# MOD-W_V02.net
KiCad netlist of a schematic drawn in EAGLE
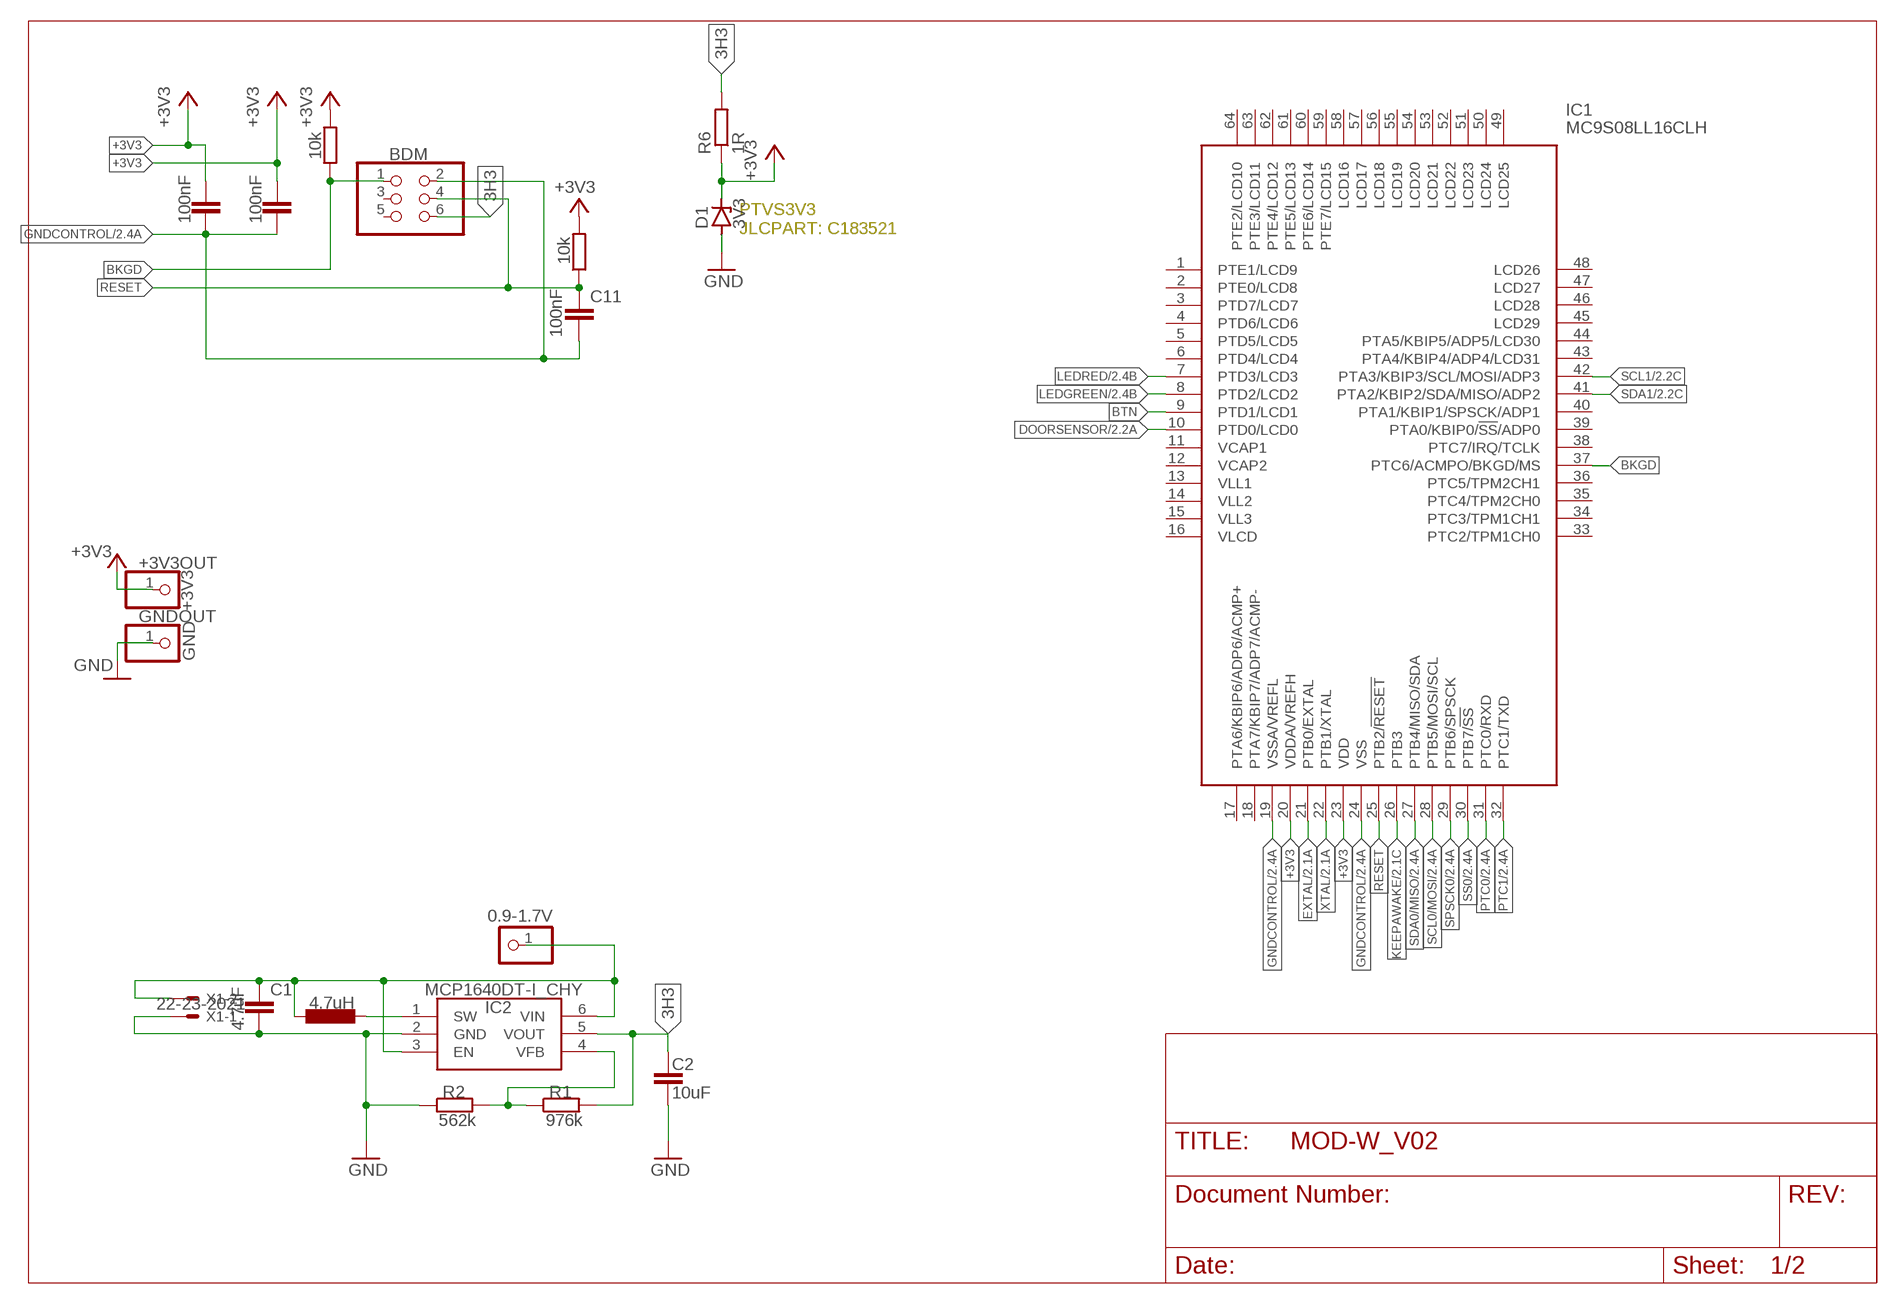
[diagram p0: schematic, sheet 1]
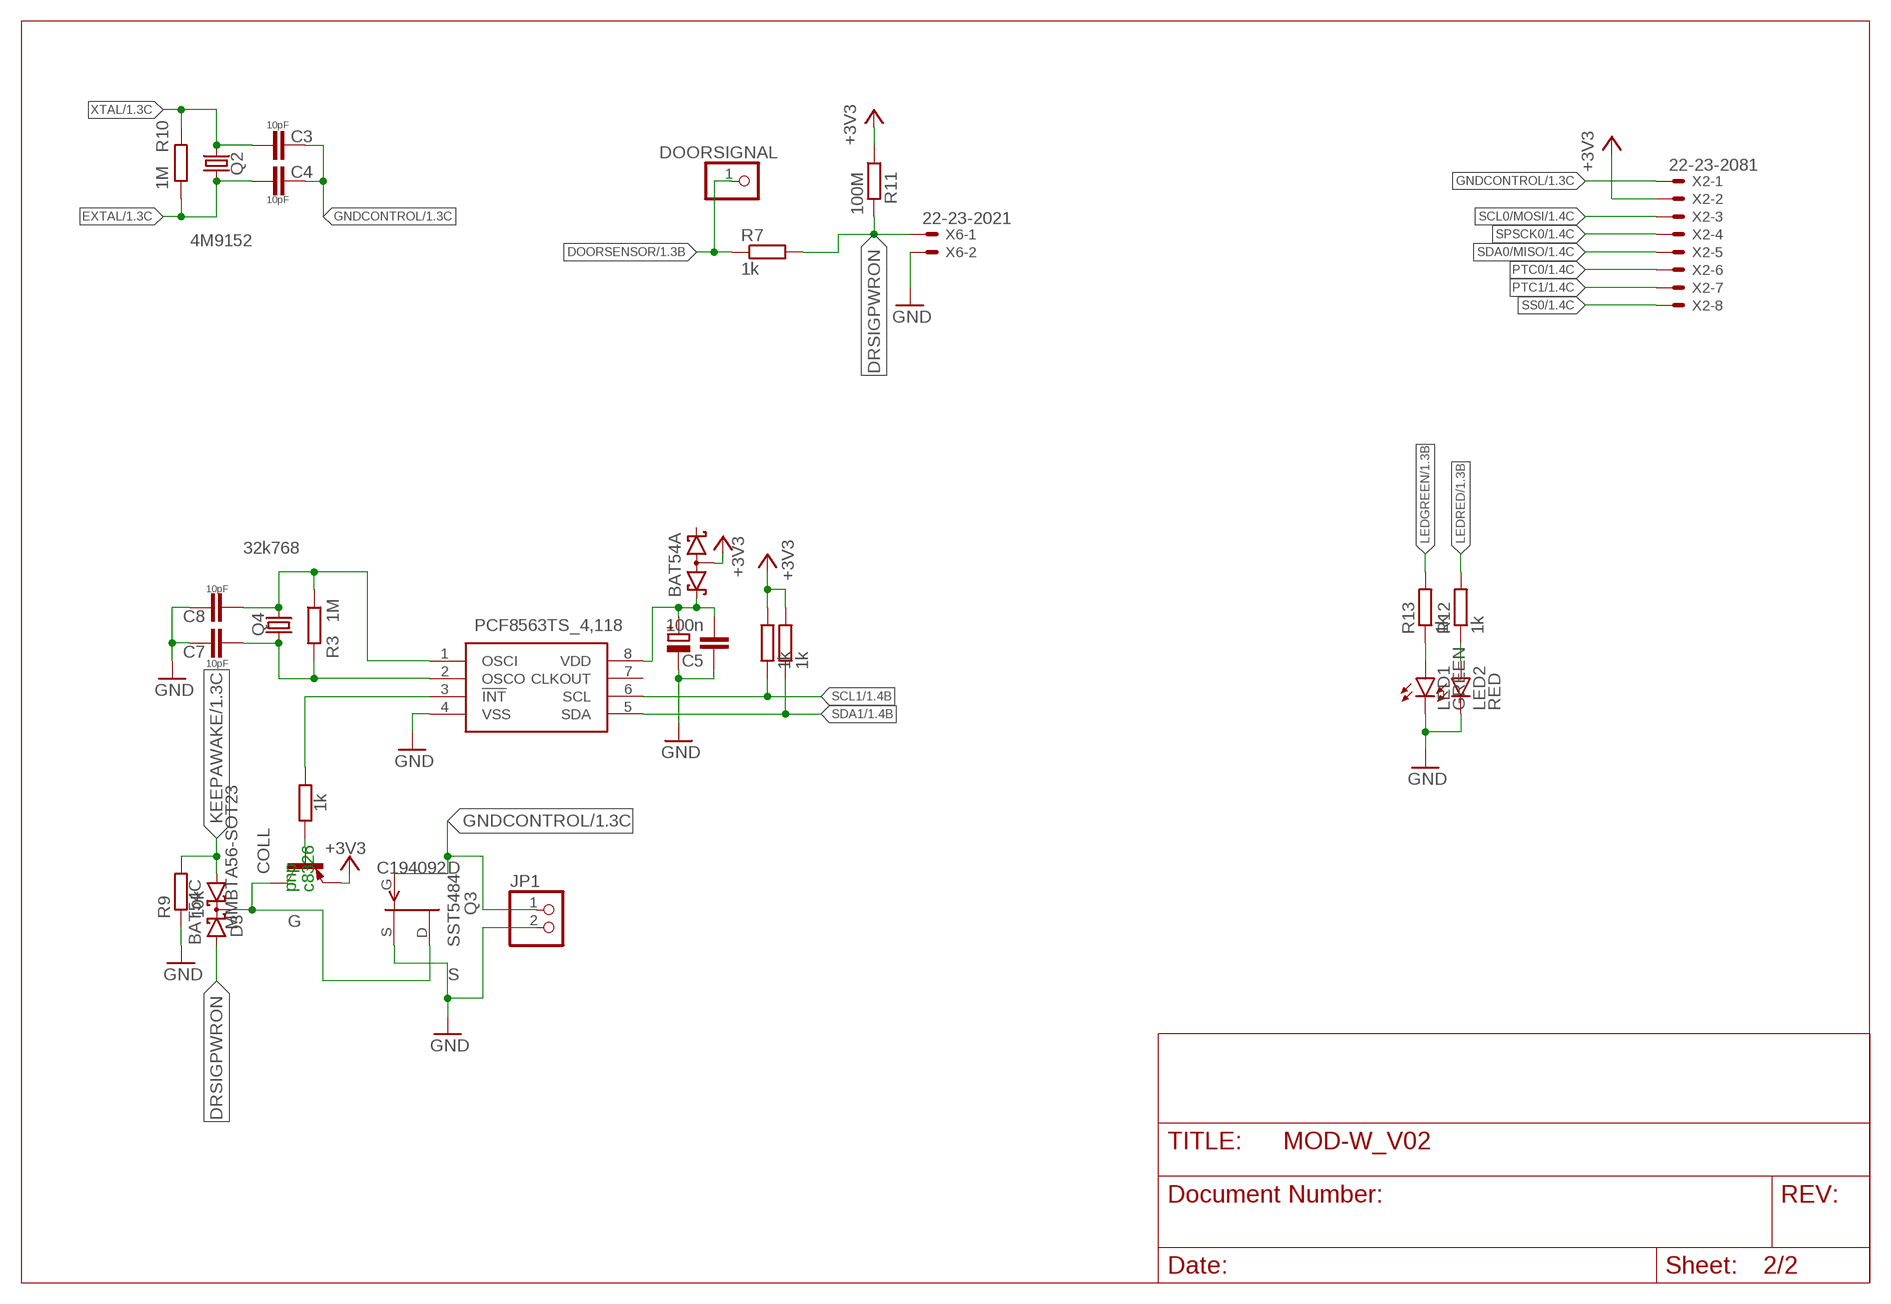
[diagram p1: schematic, sheet 2]

(export (version "E")
  (design (tool "Eeschema 10.0.6"))
  (components
    (comp (ref "+3V3OUT")
      (value "+3V3")
      (footprint "eagle-import:1X01")
      (libsource (lib "eagle-import") (part "PINHD-1X1"))
    )
    (comp (ref "BAT")
      (value "0.9-1.7V")
      (footprint "eagle-import:1X01")
      (libsource (lib "eagle-import") (part "PINHD-1X1"))
    )
    (comp (ref "BDM")
      (value "PINHD-2X3")
      (footprint "eagle-import:2X03")
      (libsource (lib "eagle-import") (part "PINHD-2X3"))
    )
    (comp (ref "C1")
      (value "4.7uF")
      (footprint "eagle-import:C0805")
      (libsource (lib "eagle-import") (part "C-EUC0805"))
    )
    (comp (ref "C2")
      (value "10uF")
      (footprint "eagle-import:C0805")
      (libsource (lib "eagle-import") (part "C-EUC0805"))
    )
    (comp (ref "C9")
      (value "100nF")
      (footprint "eagle-import:C0805")
      (libsource (lib "eagle-import") (part "C-EUC0805"))
    )
    (comp (ref "C10")
      (value "100nF")
      (footprint "eagle-import:C0805")
      (libsource (lib "eagle-import") (part "C-EUC0805"))
    )
    (comp (ref "C11")
      (value "100nF")
      (footprint "eagle-import:C0805")
      (libsource (lib "eagle-import") (part "C-EUC0805"))
    )
    (comp (ref "D1")
      (value "3V3")
      (footprint "eagle-import:SOD80C")
      (libsource (lib "eagle-import") (part "ZENER-DIODESOD80C"))
    )
    (comp (ref "GNDOUT")
      (value "GND")
      (footprint "eagle-import:1X01")
      (libsource (lib "eagle-import") (part "PINHD-1X1"))
    )
    (comp (ref "IC1")
      (value "MC9S08LL16CLH")
      (footprint "eagle-import:QFP50P1200X1200X160-64N")
      (fields (field (name "MOUSER_PART_NUMBER") "841-MC9S08LL16CLH"))
      (libsource (lib "eagle-import") (part "MC9S08LL16CLH"))
    )
    (comp (ref "IC2")
      (value "MCP1640DT-I_CHY")
      (footprint "eagle-import:SOT95P270X145-6N")
      (fields
        (field (name "ARROW_PART_NUMBER") "MCP1640DT-I/CHY")
        (field (name "MOUSER_PART_NUMBER") "579-MCP1640DT-I/CHY")
      )
      (libsource (lib "eagle-import") (part "MCP1640DT-I_CHY"))
    )
    (comp (ref "L1")
      (value "4.7uH")
      (footprint "eagle-import:L2012C")
      (libsource (lib "eagle-import") (part "L-EUL2012C"))
    )
    (comp (ref "R1")
      (value "976k")
      (footprint "eagle-import:R0805")
      (libsource (lib "eagle-import") (part "R-EU_R0805"))
    )
    (comp (ref "R2")
      (value "562k")
      (footprint "eagle-import:R0805")
      (libsource (lib "eagle-import") (part "R-EU_R0805"))
    )
    (comp (ref "R6")
      (value "1R")
      (footprint "eagle-import:R0805")
      (libsource (lib "eagle-import") (part "R-EU_R0805"))
    )
    (comp (ref "R16")
      (value "10k")
      (footprint "eagle-import:R0805")
      (libsource (lib "eagle-import") (part "R-EU_R0805"))
    )
    (comp (ref "R17")
      (value "10k")
      (footprint "eagle-import:R0805")
      (libsource (lib "eagle-import") (part "R-EU_R0805"))
    )
    (comp (ref "X1")
      (value "22-23-2021")
      (footprint "eagle-import:22-23-2021")
      (fields (field (name "MF") "MOLEX"))
      (libsource (lib "eagle-import") (part "22-23-2021"))
    )
    (comp (ref "C3")
      (value "10pF")
      (footprint "eagle-import:C0805")
      (libsource (lib "eagle-import") (part "C-EUC0805"))
    )
    (comp (ref "C4")
      (value "10pF")
      (footprint "eagle-import:C0805")
      (libsource (lib "eagle-import") (part "C-EUC0805"))
    )
    (comp (ref "C5")
      (value "100n")
      (footprint "eagle-import:C0805")
      (libsource (lib "eagle-import") (part "C-EUC0805"))
    )
    (comp (ref "C6")
      (value "100u")
      (footprint "eagle-import:PANASONIC_E")
      (libsource (lib "eagle-import") (part "CPOL-EUE"))
    )
    (comp (ref "C7")
      (value "10pF")
      (footprint "eagle-import:C0805")
      (libsource (lib "eagle-import") (part "C-EUC0805"))
    )
    (comp (ref "C8")
      (value "10pF")
      (footprint "eagle-import:C0805")
      (libsource (lib "eagle-import") (part "C-EUC0805"))
    )
    (comp (ref "D2")
      (value "BAT54A")
      (footprint "eagle-import:SOT23")
      (libsource (lib "eagle-import") (part "BAT54A"))
    )
    (comp (ref "D3")
      (value "BAT54C")
      (footprint "eagle-import:SOT23")
      (libsource (lib "eagle-import") (part "BAT54C"))
    )
    (comp (ref "DOORSIGNAL")
      (value "PINHD-1X1")
      (footprint "eagle-import:1X01")
      (libsource (lib "eagle-import") (part "PINHD-1X1"))
    )
    (comp (ref "IC3")
      (value "PCF8563TS_4,118")
      (footprint "eagle-import:SOP65P490X110-8N")
      (fields
        (field (name "ARROW_PART_NUMBER") "PCF8563TS/4,118")
        (field (name "MOUSER_PART_NUMBER") "771-PCF8563TS-T")
      )
      (libsource (lib "eagle-import") (part "PCF8563TS_4,118"))
    )
    (comp (ref "JP1")
      (value "PINHD-1X2")
      (footprint "eagle-import:1X02")
      (libsource (lib "eagle-import") (part "PINHD-1X2"))
    )
    (comp (ref "LED1")
      (value "GREEN")
      (footprint "eagle-import:CHIP-LED0805")
      (libsource (lib "eagle-import") (part "LEDCHIP-LED0805"))
    )
    (comp (ref "LED2")
      (value "RED")
      (footprint "eagle-import:CHIP-LED0805")
      (libsource (lib "eagle-import") (part "LEDCHIP-LED0805"))
    )
    (comp (ref "Q1")
      (value "MMBTA56-SOT23")
      (footprint "eagle-import:SOT23")
      (libsource (lib "eagle-import") (part "-?SOT23MMBTA56"))
    )
    (comp (ref "Q2")
      (value "4M9152")
      (footprint "eagle-import:HC49UP")
      (libsource (lib "eagle-import") (part "CRYSTALHC49UP"))
    )
    (comp (ref "Q3")
      (value "SST5484")
      (footprint "eagle-import:SOT23")
      (libsource (lib "eagle-import") (part "?548SST4"))
    )
    (comp (ref "Q4")
      (value "32k768")
      (footprint "eagle-import:TC38H")
      (libsource (lib "eagle-import") (part "CRYSTALTC38H"))
    )
    (comp (ref "R3")
      (value "1M")
      (footprint "eagle-import:R0805")
      (libsource (lib "eagle-import") (part "R-EU_R0805"))
    )
    (comp (ref "R4")
      (value "1k")
      (footprint "eagle-import:R0805")
      (libsource (lib "eagle-import") (part "R-EU_R0805"))
    )
    (comp (ref "R5")
      (value "1k")
      (footprint "eagle-import:R0805")
      (libsource (lib "eagle-import") (part "R-EU_R0805"))
    )
    (comp (ref "R7")
      (value "1k")
      (footprint "eagle-import:R0805")
      (libsource (lib "eagle-import") (part "R-EU_R0805"))
    )
    (comp (ref "R8")
      (value "1k")
      (footprint "eagle-import:R0805")
      (libsource (lib "eagle-import") (part "R-EU_R0805"))
    )
    (comp (ref "R9")
      (value "10k")
      (footprint "eagle-import:R0805")
      (libsource (lib "eagle-import") (part "R-EU_R0805"))
    )
    (comp (ref "R10")
      (value "1M")
      (footprint "eagle-import:R0805")
      (libsource (lib "eagle-import") (part "R-EU_R0805"))
    )
    (comp (ref "R11")
      (value "100M")
      (footprint "eagle-import:R0805")
      (libsource (lib "eagle-import") (part "R-EU_R0805"))
    )
    (comp (ref "R12")
      (value "1k")
      (footprint "eagle-import:R0805")
      (libsource (lib "eagle-import") (part "R-EU_R0805"))
    )
    (comp (ref "R13")
      (value "1k")
      (footprint "eagle-import:R0805")
      (libsource (lib "eagle-import") (part "R-EU_R0805"))
    )
    (comp (ref "X2")
      (value "22-23-2081")
      (footprint "eagle-import:22-23-2081")
      (fields (field (name "MF") "MOLEX"))
      (libsource (lib "eagle-import") (part "22-23-2081"))
    )
    (comp (ref "X6")
      (value "22-23-2021")
      (footprint "eagle-import:22-23-2021")
      (fields (field (name "MF") "MOLEX"))
      (libsource (lib "eagle-import") (part "22-23-2021"))
    )
  )
  (nets
    (net (code "1") (name "+3V3") (class "Default")
      (node (ref "+3V3OUT") (pin "1") (pinfunction "1_1") (pintype "passive"))
      (node (ref "C10") (pin "1") (pinfunction "1_1") (pintype "passive"))
      (node (ref "C9") (pin "1") (pinfunction "1_1") (pintype "passive"))
      (node (ref "D1") (pin "C") (pinfunction "C_C") (pintype "passive"))
      (node (ref "D2") (pin "3") (pinfunction "AA_3") (pintype "passive"))
      (node (ref "IC1") (pin "20") (pinfunction "VDDA/VREFH_20") (pintype "bidirectional"))
      (node (ref "IC1") (pin "23") (pinfunction "VDD_23") (pintype "bidirectional"))
      (node (ref "Q1") (pin "2") (pinfunction "E_2") (pintype "passive"))
      (node (ref "R11") (pin "1") (pinfunction "1_1") (pintype "passive"))
      (node (ref "R16") (pin "2") (pinfunction "2_2") (pintype "passive"))
      (node (ref "R17") (pin "2") (pinfunction "2_2") (pintype "passive"))
      (node (ref "R4") (pin "2") (pinfunction "2_2") (pintype "passive"))
      (node (ref "R5") (pin "2") (pinfunction "2_2") (pintype "passive"))
      (node (ref "R6") (pin "1") (pinfunction "1_1") (pintype "passive"))
      (node (ref "X2") (pin "2") (pinfunction "S_2") (pintype "passive"))
    )
    (net (code "2") (name "3H3") (class "Default")
      (node (ref "BDM") (pin "6") (pinfunction "6_6") (pintype "passive"))
      (node (ref "C2") (pin "1") (pinfunction "1_1") (pintype "passive"))
      (node (ref "IC2") (pin "5") (pinfunction "VOUT_5") (pintype "output"))
      (node (ref "R1") (pin "2") (pinfunction "2_2") (pintype "passive"))
      (node (ref "R6") (pin "2") (pinfunction "2_2") (pintype "passive"))
    )
    (net (code "3") (name "BKGD") (class "Default")
      (node (ref "BDM") (pin "1") (pinfunction "1_1") (pintype "passive"))
      (node (ref "IC1") (pin "37") (pinfunction "PTC6/ACMPO/BKGD/MS_37") (pintype "bidirectional"))
      (node (ref "R16") (pin "1") (pinfunction "1_1") (pintype "passive"))
    )
    (net (code "4") (name "BTN") (class "Default")
      (node (ref "IC1") (pin "9") (pinfunction "PTD1/LCD1_9") (pintype "bidirectional"))
    )
    (net (code "5") (name "COLL") (class "Default")
      (node (ref "D3") (pin "3") (pinfunction "CC_3") (pintype "passive"))
      (node (ref "Q1") (pin "3") (pinfunction "C_3") (pintype "passive"))
      (node (ref "Q3") (pin "1") (pinfunction "D_1") (pintype "passive"))
    )
    (net (code "6") (name "DOORSENSOR") (class "Default")
      (node (ref "DOORSIGNAL") (pin "1") (pinfunction "1_1") (pintype "passive"))
      (node (ref "IC1") (pin "10") (pinfunction "PTD0/LCD0_10") (pintype "bidirectional"))
      (node (ref "R7") (pin "1") (pinfunction "1_1") (pintype "passive"))
    )
    (net (code "7") (name "DRSIGPWRON") (class "Default")
      (node (ref "D3") (pin "2") (pinfunction "A2_2") (pintype "passive"))
      (node (ref "R11") (pin "2") (pinfunction "2_2") (pintype "passive"))
      (node (ref "R7") (pin "2") (pinfunction "2_2") (pintype "passive"))
      (node (ref "X6") (pin "1") (pinfunction "S_1") (pintype "passive"))
    )
    (net (code "8") (name "EXTAL") (class "Default")
      (node (ref "C4") (pin "1") (pinfunction "1_1") (pintype "passive"))
      (node (ref "IC1") (pin "21") (pinfunction "PTB0/EXTAL_21") (pintype "bidirectional"))
      (node (ref "Q2") (pin "1") (pinfunction "1_1") (pintype "passive"))
      (node (ref "R10") (pin "1") (pinfunction "1_1") (pintype "passive"))
    )
    (net (code "9") (name "GND") (class "Default")
      (node (ref "C1") (pin "2") (pinfunction "2_2") (pintype "passive"))
      (node (ref "C2") (pin "2") (pinfunction "2_2") (pintype "passive"))
      (node (ref "C5") (pin "1") (pinfunction "1_1") (pintype "passive"))
      (node (ref "C6") (pin "-") (pinfunction "-_-") (pintype "passive"))
      (node (ref "C7") (pin "2") (pinfunction "2_2") (pintype "passive"))
      (node (ref "C8") (pin "2") (pinfunction "2_2") (pintype "passive"))
      (node (ref "D1") (pin "A") (pinfunction "A_A") (pintype "passive"))
      (node (ref "GNDOUT") (pin "1") (pinfunction "1_1") (pintype "passive"))
      (node (ref "IC2") (pin "2") (pinfunction "GND_2") (pintype "power_in"))
      (node (ref "IC3") (pin "4") (pinfunction "VSS_4") (pintype "bidirectional"))
      (node (ref "JP1") (pin "2") (pinfunction "2_2") (pintype "passive"))
      (node (ref "LED1") (pin "C") (pinfunction "C_C") (pintype "passive"))
      (node (ref "LED2") (pin "C") (pinfunction "C_C") (pintype "passive"))
      (node (ref "Q3") (pin "2") (pinfunction "S_2") (pintype "passive"))
      (node (ref "R2") (pin "1") (pinfunction "1_1") (pintype "passive"))
      (node (ref "R9") (pin "1") (pinfunction "1_1") (pintype "passive"))
      (node (ref "X1") (pin "1") (pinfunction "S_1") (pintype "passive"))
      (node (ref "X6") (pin "2") (pinfunction "S_2") (pintype "passive"))
    )
    (net (code "10") (name "GNDCONTROL") (class "Default")
      (node (ref "BDM") (pin "2") (pinfunction "2_2") (pintype "passive"))
      (node (ref "C10") (pin "2") (pinfunction "2_2") (pintype "passive"))
      (node (ref "C11") (pin "2") (pinfunction "2_2") (pintype "passive"))
      (node (ref "C3") (pin "2") (pinfunction "2_2") (pintype "passive"))
      (node (ref "C4") (pin "2") (pinfunction "2_2") (pintype "passive"))
      (node (ref "C9") (pin "2") (pinfunction "2_2") (pintype "passive"))
      (node (ref "IC1") (pin "19") (pinfunction "VSSA/VREFL_19") (pintype "bidirectional"))
      (node (ref "IC1") (pin "24") (pinfunction "VSS_24") (pintype "bidirectional"))
      (node (ref "JP1") (pin "1") (pinfunction "1_1") (pintype "passive"))
      (node (ref "Q3") (pin "3") (pinfunction "G_3") (pintype "passive"))
      (node (ref "X2") (pin "1") (pinfunction "S_1") (pintype "passive"))
    )
    (net (code "11") (name "KEEPAWAKE") (class "Default")
      (node (ref "D3") (pin "1") (pinfunction "A1_1") (pintype "passive"))
      (node (ref "IC1") (pin "26") (pinfunction "PTB3_26") (pintype "bidirectional"))
      (node (ref "R9") (pin "2") (pinfunction "2_2") (pintype "passive"))
    )
    (net (code "12") (name "LEDGREEN") (class "Default")
      (node (ref "IC1") (pin "8") (pinfunction "PTD2/LCD2_8") (pintype "bidirectional"))
      (node (ref "R13") (pin "2") (pinfunction "2_2") (pintype "passive"))
    )
    (net (code "13") (name "LEDRED") (class "Default")
      (node (ref "IC1") (pin "7") (pinfunction "PTD3/LCD3_7") (pintype "bidirectional"))
      (node (ref "R12") (pin "2") (pinfunction "2_2") (pintype "passive"))
    )
    (net (code "14") (name "Net-(D2-K2)") (class "Default")
      (node (ref "C5") (pin "2") (pinfunction "2_2") (pintype "passive"))
      (node (ref "C6") (pin "+") (pinfunction "+_+") (pintype "passive"))
      (node (ref "D2") (pin "2") (pinfunction "K2_2") (pintype "passive"))
      (node (ref "IC3") (pin "8") (pinfunction "VDD_8") (pintype "bidirectional"))
    )
    (net (code "15") (name "Net-(IC2-EN)") (class "Default")
      (node (ref "BAT") (pin "1") (pinfunction "1_1") (pintype "passive"))
      (node (ref "C1") (pin "1") (pinfunction "1_1") (pintype "passive"))
      (node (ref "IC2") (pin "3") (pinfunction "EN_3") (pintype "power_in"))
      (node (ref "IC2") (pin "6") (pinfunction "VIN_6") (pintype "input"))
      (node (ref "L1") (pin "2") (pinfunction "2_2") (pintype "passive"))
      (node (ref "X1") (pin "2") (pinfunction "S_2") (pintype "passive"))
    )
    (net (code "16") (name "Net-(IC2-SW)") (class "Default")
      (node (ref "IC2") (pin "1") (pinfunction "SW_1") (pintype "input"))
      (node (ref "L1") (pin "1") (pinfunction "1_1") (pintype "passive"))
    )
    (net (code "17") (name "Net-(IC2-VFB)") (class "Default")
      (node (ref "IC2") (pin "4") (pinfunction "VFB_4") (pintype "bidirectional"))
      (node (ref "R1") (pin "1") (pinfunction "1_1") (pintype "passive"))
      (node (ref "R2") (pin "2") (pinfunction "2_2") (pintype "passive"))
    )
    (net (code "18") (name "Net-(IC3-OSCI)") (class "Default")
      (node (ref "C8") (pin "1") (pinfunction "1_1") (pintype "passive"))
      (node (ref "IC3") (pin "1") (pinfunction "OSCI_1") (pintype "bidirectional"))
      (node (ref "Q4") (pin "1") (pinfunction "1_1") (pintype "passive"))
      (node (ref "R3") (pin "1") (pinfunction "1_1") (pintype "passive"))
    )
    (net (code "19") (name "Net-(IC3-OSCO)") (class "Default")
      (node (ref "C7") (pin "1") (pinfunction "1_1") (pintype "passive"))
      (node (ref "IC3") (pin "2") (pinfunction "OSCO_2") (pintype "bidirectional"))
      (node (ref "Q4") (pin "2") (pinfunction "2_2") (pintype "passive"))
      (node (ref "R3") (pin "2") (pinfunction "2_2") (pintype "passive"))
    )
    (net (code "20") (name "Net-(IC3-~{INT})") (class "Default")
      (node (ref "IC3") (pin "3") (pinfunction "~{INT}_3") (pintype "bidirectional"))
      (node (ref "R8") (pin "2") (pinfunction "2_2") (pintype "passive"))
    )
    (net (code "21") (name "Net-(LED1-PadA)") (class "Default")
      (node (ref "LED1") (pin "A") (pinfunction "A_A") (pintype "passive"))
      (node (ref "R13") (pin "1") (pinfunction "1_1") (pintype "passive"))
    )
    (net (code "22") (name "Net-(LED2-PadA)") (class "Default")
      (node (ref "LED2") (pin "A") (pinfunction "A_A") (pintype "passive"))
      (node (ref "R12") (pin "1") (pinfunction "1_1") (pintype "passive"))
    )
    (net (code "23") (name "Net-(Q1-B)") (class "Default")
      (node (ref "Q1") (pin "1") (pinfunction "B_1") (pintype "passive"))
      (node (ref "R8") (pin "1") (pinfunction "1_1") (pintype "passive"))
    )
    (net (code "24") (name "PTC0") (class "Default")
      (node (ref "IC1") (pin "31") (pinfunction "PTC0/RXD_31") (pintype "bidirectional"))
      (node (ref "X2") (pin "6") (pinfunction "S_6") (pintype "passive"))
    )
    (net (code "25") (name "PTC1") (class "Default")
      (node (ref "IC1") (pin "32") (pinfunction "PTC1/TXD_32") (pintype "bidirectional"))
      (node (ref "X2") (pin "7") (pinfunction "S_7") (pintype "passive"))
    )
    (net (code "26") (name "RESET") (class "Default")
      (node (ref "BDM") (pin "4") (pinfunction "4_4") (pintype "passive"))
      (node (ref "C11") (pin "1") (pinfunction "1_1") (pintype "passive"))
      (node (ref "IC1") (pin "25") (pinfunction "PTB2/~{RESET}_25") (pintype "bidirectional"))
      (node (ref "R17") (pin "1") (pinfunction "1_1") (pintype "passive"))
    )
    (net (code "27") (name "SCL0{slash}MOSI") (class "Default")
      (node (ref "IC1") (pin "28") (pinfunction "PTB5/MOSI/SCL_28") (pintype "bidirectional"))
      (node (ref "X2") (pin "3") (pinfunction "S_3") (pintype "passive"))
    )
    (net (code "28") (name "SCL1") (class "Default")
      (node (ref "IC1") (pin "42") (pinfunction "PTA3/KBIP3/SCL/MOSI/ADP3_42") (pintype "bidirectional"))
      (node (ref "IC3") (pin "6") (pinfunction "SCL_6") (pintype "bidirectional"))
      (node (ref "R4") (pin "1") (pinfunction "1_1") (pintype "passive"))
    )
    (net (code "29") (name "SDA0{slash}MISO") (class "Default")
      (node (ref "IC1") (pin "27") (pinfunction "PTB4/MISO/SDA_27") (pintype "bidirectional"))
      (node (ref "X2") (pin "5") (pinfunction "S_5") (pintype "passive"))
    )
    (net (code "30") (name "SDA1") (class "Default")
      (node (ref "IC1") (pin "41") (pinfunction "PTA2/KBIP2/SDA/MISO/ADP2_41") (pintype "bidirectional"))
      (node (ref "IC3") (pin "5") (pinfunction "SDA_5") (pintype "bidirectional"))
      (node (ref "R5") (pin "1") (pinfunction "1_1") (pintype "passive"))
    )
    (net (code "31") (name "SPSCK0") (class "Default")
      (node (ref "IC1") (pin "29") (pinfunction "PTB6/SPSCK_29") (pintype "bidirectional"))
      (node (ref "X2") (pin "4") (pinfunction "S_4") (pintype "passive"))
    )
    (net (code "32") (name "SS0") (class "Default")
      (node (ref "IC1") (pin "30") (pinfunction "PTB7/~{SS}_30") (pintype "bidirectional"))
      (node (ref "X2") (pin "8") (pinfunction "S_8") (pintype "passive"))
    )
    (net (code "33") (name "XTAL") (class "Default")
      (node (ref "C3") (pin "1") (pinfunction "1_1") (pintype "passive"))
      (node (ref "IC1") (pin "22") (pinfunction "PTB1/XTAL_22") (pintype "bidirectional"))
      (node (ref "Q2") (pin "2") (pinfunction "2_2") (pintype "passive"))
      (node (ref "R10") (pin "2") (pinfunction "2_2") (pintype "passive"))
    )
    (net (code "34") (name "unconnected-(BDM-Pad3)") (class "Default")
      (node (ref "BDM") (pin "3") (pinfunction "3_3") (pintype "passive"))
    )
    (net (code "35") (name "unconnected-(BDM-Pad5)") (class "Default")
      (node (ref "BDM") (pin "5") (pinfunction "5_5") (pintype "passive"))
    )
    (net (code "36") (name "unconnected-(D2-K1-Pad1)") (class "Default")
      (node (ref "D2") (pin "1") (pinfunction "K1_1") (pintype "passive"))
    )
    (net (code "37") (name "unconnected-(IC1-LCD16-Pad58)") (class "Default")
      (node (ref "IC1") (pin "58") (pinfunction "LCD16_58") (pintype "bidirectional"))
    )
    (net (code "38") (name "unconnected-(IC1-LCD17-Pad57)") (class "Default")
      (node (ref "IC1") (pin "57") (pinfunction "LCD17_57") (pintype "bidirectional"))
    )
    (net (code "39") (name "unconnected-(IC1-LCD18-Pad56)") (class "Default")
      (node (ref "IC1") (pin "56") (pinfunction "LCD18_56") (pintype "bidirectional"))
    )
    (net (code "40") (name "unconnected-(IC1-LCD19-Pad55)") (class "Default")
      (node (ref "IC1") (pin "55") (pinfunction "LCD19_55") (pintype "bidirectional"))
    )
    (net (code "41") (name "unconnected-(IC1-LCD20-Pad54)") (class "Default")
      (node (ref "IC1") (pin "54") (pinfunction "LCD20_54") (pintype "bidirectional"))
    )
    (net (code "42") (name "unconnected-(IC1-LCD21-Pad53)") (class "Default")
      (node (ref "IC1") (pin "53") (pinfunction "LCD21_53") (pintype "bidirectional"))
    )
    (net (code "43") (name "unconnected-(IC1-LCD22-Pad52)") (class "Default")
      (node (ref "IC1") (pin "52") (pinfunction "LCD22_52") (pintype "bidirectional"))
    )
    (net (code "44") (name "unconnected-(IC1-LCD23-Pad51)") (class "Default")
      (node (ref "IC1") (pin "51") (pinfunction "LCD23_51") (pintype "bidirectional"))
    )
    (net (code "45") (name "unconnected-(IC1-LCD24-Pad50)") (class "Default")
      (node (ref "IC1") (pin "50") (pinfunction "LCD24_50") (pintype "bidirectional"))
    )
    (net (code "46") (name "unconnected-(IC1-LCD25-Pad49)") (class "Default")
      (node (ref "IC1") (pin "49") (pinfunction "LCD25_49") (pintype "bidirectional"))
    )
    (net (code "47") (name "unconnected-(IC1-LCD26-Pad48)") (class "Default")
      (node (ref "IC1") (pin "48") (pinfunction "LCD26_48") (pintype "bidirectional"))
    )
    (net (code "48") (name "unconnected-(IC1-LCD27-Pad47)") (class "Default")
      (node (ref "IC1") (pin "47") (pinfunction "LCD27_47") (pintype "bidirectional"))
    )
    (net (code "49") (name "unconnected-(IC1-LCD28-Pad46)") (class "Default")
      (node (ref "IC1") (pin "46") (pinfunction "LCD28_46") (pintype "bidirectional"))
    )
    (net (code "50") (name "unconnected-(IC1-LCD29-Pad45)") (class "Default")
      (node (ref "IC1") (pin "45") (pinfunction "LCD29_45") (pintype "bidirectional"))
    )
    (net (code "51") (name "unconnected-(IC1-PTA0{slash}KBIP0{slash}~{SS}{slash}ADP0-Pad39)") (class "Default")
      (node (ref "IC1") (pin "39") (pinfunction "PTA0/KBIP0/~{SS}/ADP0_39") (pintype "bidirectional"))
    )
    (net (code "52") (name "unconnected-(IC1-PTA1{slash}KBIP1{slash}SPSCK{slash}ADP1-Pad40)") (class "Default")
      (node (ref "IC1") (pin "40") (pinfunction "PTA1/KBIP1/SPSCK/ADP1_40") (pintype "bidirectional"))
    )
    (net (code "53") (name "unconnected-(IC1-PTA4{slash}KBIP4{slash}ADP4{slash}LCD31-Pad43)") (class "Default")
      (node (ref "IC1") (pin "43") (pinfunction "PTA4/KBIP4/ADP4/LCD31_43") (pintype "bidirectional"))
    )
    (net (code "54") (name "unconnected-(IC1-PTA5{slash}KBIP5{slash}ADP5{slash}LCD30-Pad44)") (class "Default")
      (node (ref "IC1") (pin "44") (pinfunction "PTA5/KBIP5/ADP5/LCD30_44") (pintype "bidirectional"))
    )
    (net (code "55") (name "unconnected-(IC1-PTA6{slash}KBIP6{slash}ADP6{slash}ACMP+-Pad17)") (class "Default")
      (node (ref "IC1") (pin "17") (pinfunction "PTA6/KBIP6/ADP6/ACMP+_17") (pintype "bidirectional"))
    )
    (net (code "56") (name "unconnected-(IC1-PTA7{slash}KBIP7{slash}ADP7{slash}ACMP--Pad18)") (class "Default")
      (node (ref "IC1") (pin "18") (pinfunction "PTA7/KBIP7/ADP7/ACMP-_18") (pintype "bidirectional"))
    )
    (net (code "57") (name "unconnected-(IC1-PTC2{slash}TPM1CH0-Pad33)") (class "Default")
      (node (ref "IC1") (pin "33") (pinfunction "PTC2/TPM1CH0_33") (pintype "bidirectional"))
    )
    (net (code "58") (name "unconnected-(IC1-PTC3{slash}TPM1CH1-Pad34)") (class "Default")
      (node (ref "IC1") (pin "34") (pinfunction "PTC3/TPM1CH1_34") (pintype "bidirectional"))
    )
    (net (code "59") (name "unconnected-(IC1-PTC4{slash}TPM2CH0-Pad35)") (class "Default")
      (node (ref "IC1") (pin "35") (pinfunction "PTC4/TPM2CH0_35") (pintype "bidirectional"))
    )
    (net (code "60") (name "unconnected-(IC1-PTC5{slash}TPM2CH1-Pad36)") (class "Default")
      (node (ref "IC1") (pin "36") (pinfunction "PTC5/TPM2CH1_36") (pintype "bidirectional"))
    )
    (net (code "61") (name "unconnected-(IC1-PTC7{slash}IRQ{slash}TCLK-Pad38)") (class "Default")
      (node (ref "IC1") (pin "38") (pinfunction "PTC7/IRQ/TCLK_38") (pintype "bidirectional"))
    )
    (net (code "62") (name "unconnected-(IC1-PTD4{slash}LCD4-Pad6)") (class "Default")
      (node (ref "IC1") (pin "6") (pinfunction "PTD4/LCD4_6") (pintype "bidirectional"))
    )
    (net (code "63") (name "unconnected-(IC1-PTD5{slash}LCD5-Pad5)") (class "Default")
      (node (ref "IC1") (pin "5") (pinfunction "PTD5/LCD5_5") (pintype "bidirectional"))
    )
    (net (code "64") (name "unconnected-(IC1-PTD6{slash}LCD6-Pad4)") (class "Default")
      (node (ref "IC1") (pin "4") (pinfunction "PTD6/LCD6_4") (pintype "bidirectional"))
    )
    (net (code "65") (name "unconnected-(IC1-PTD7{slash}LCD7-Pad3)") (class "Default")
      (node (ref "IC1") (pin "3") (pinfunction "PTD7/LCD7_3") (pintype "bidirectional"))
    )
    (net (code "66") (name "unconnected-(IC1-PTE0{slash}LCD8-Pad2)") (class "Default")
      (node (ref "IC1") (pin "2") (pinfunction "PTE0/LCD8_2") (pintype "bidirectional"))
    )
    (net (code "67") (name "unconnected-(IC1-PTE1{slash}LCD9-Pad1)") (class "Default")
      (node (ref "IC1") (pin "1") (pinfunction "PTE1/LCD9_1") (pintype "bidirectional"))
    )
    (net (code "68") (name "unconnected-(IC1-PTE2{slash}LCD10-Pad64)") (class "Default")
      (node (ref "IC1") (pin "64") (pinfunction "PTE2/LCD10_64") (pintype "bidirectional"))
    )
    (net (code "69") (name "unconnected-(IC1-PTE3{slash}LCD11-Pad63)") (class "Default")
      (node (ref "IC1") (pin "63") (pinfunction "PTE3/LCD11_63") (pintype "bidirectional"))
    )
    (net (code "70") (name "unconnected-(IC1-PTE4{slash}LCD12-Pad62)") (class "Default")
      (node (ref "IC1") (pin "62") (pinfunction "PTE4/LCD12_62") (pintype "bidirectional"))
    )
    (net (code "71") (name "unconnected-(IC1-PTE5{slash}LCD13-Pad61)") (class "Default")
      (node (ref "IC1") (pin "61") (pinfunction "PTE5/LCD13_61") (pintype "bidirectional"))
    )
    (net (code "72") (name "unconnected-(IC1-PTE6{slash}LCD14-Pad60)") (class "Default")
      (node (ref "IC1") (pin "60") (pinfunction "PTE6/LCD14_60") (pintype "bidirectional"))
    )
    (net (code "73") (name "unconnected-(IC1-PTE7{slash}LCD15-Pad59)") (class "Default")
      (node (ref "IC1") (pin "59") (pinfunction "PTE7/LCD15_59") (pintype "bidirectional"))
    )
    (net (code "74") (name "unconnected-(IC1-VCAP1-Pad11)") (class "Default")
      (node (ref "IC1") (pin "11") (pinfunction "VCAP1_11") (pintype "bidirectional"))
    )
    (net (code "75") (name "unconnected-(IC1-VCAP2-Pad12)") (class "Default")
      (node (ref "IC1") (pin "12") (pinfunction "VCAP2_12") (pintype "bidirectional"))
    )
    (net (code "76") (name "unconnected-(IC1-VLCD-Pad16)") (class "Default")
      (node (ref "IC1") (pin "16") (pinfunction "VLCD_16") (pintype "bidirectional"))
    )
    (net (code "77") (name "unconnected-(IC1-VLL1-Pad13)") (class "Default")
      (node (ref "IC1") (pin "13") (pinfunction "VLL1_13") (pintype "bidirectional"))
    )
    (net (code "78") (name "unconnected-(IC1-VLL2-Pad14)") (class "Default")
      (node (ref "IC1") (pin "14") (pinfunction "VLL2_14") (pintype "bidirectional"))
    )
    (net (code "79") (name "unconnected-(IC1-VLL3-Pad15)") (class "Default")
      (node (ref "IC1") (pin "15") (pinfunction "VLL3_15") (pintype "bidirectional"))
    )
    (net (code "80") (name "unconnected-(IC3-CLKOUT-Pad7)") (class "Default")
      (node (ref "IC3") (pin "7") (pinfunction "CLKOUT_7") (pintype "bidirectional"))
    )
  )
)
